# 06_LEDs.net
KiCad netlist of a schematic drawn in Altium Designer
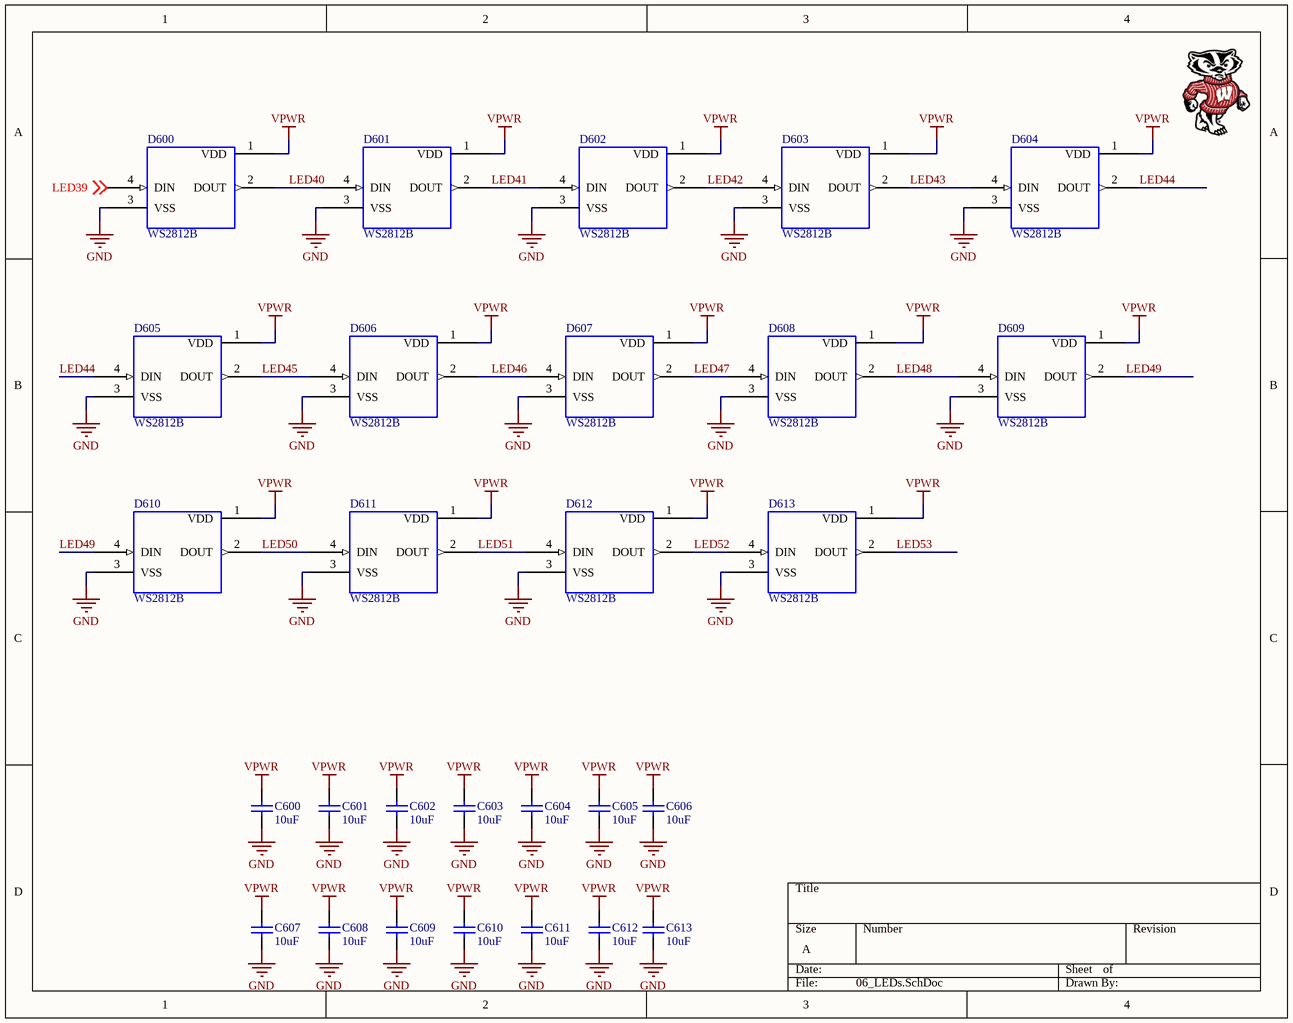
[diagram p0: 06_LEDs.SchDoc]

(export (version "E")
  (design (tool "Eeschema 10.0.6"))
  (components
    (comp (ref "C600")
      (value "10uF")
      (footprint "CAP_0805")
      (description "CAP CER 10UF 16V X7R 0805")
      (fields
        (field (name "MANUFACTURER") "Samsung")
        (field (name "MANUFACTURER PART NUMBER") "CL21A106KPCLQNC")
        (field (name "CAPACITANCE") "10uF")
      )
      (libsource (lib "ece315-2018-fall") (part "CAP_0805_U_010.00"))
    )
    (comp (ref "C601")
      (value "10uF")
      (footprint "CAP_0805")
      (description "CAP CER 10UF 16V X7R 0805")
      (fields
        (field (name "MANUFACTURER") "Samsung")
        (field (name "MANUFACTURER PART NUMBER") "CL21A106KPCLQNC")
        (field (name "CAPACITANCE") "10uF")
      )
      (libsource (lib "ece315-2018-fall") (part "CAP_0805_U_010.00"))
    )
    (comp (ref "C602")
      (value "10uF")
      (footprint "CAP_0805")
      (description "CAP CER 10UF 16V X7R 0805")
      (fields
        (field (name "MANUFACTURER") "Samsung")
        (field (name "MANUFACTURER PART NUMBER") "CL21A106KPCLQNC")
        (field (name "CAPACITANCE") "10uF")
      )
      (libsource (lib "ece315-2018-fall") (part "CAP_0805_U_010.00"))
    )
    (comp (ref "C603")
      (value "10uF")
      (footprint "CAP_0805")
      (description "CAP CER 10UF 16V X7R 0805")
      (fields
        (field (name "MANUFACTURER") "Samsung")
        (field (name "MANUFACTURER PART NUMBER") "CL21A106KPCLQNC")
        (field (name "CAPACITANCE") "10uF")
      )
      (libsource (lib "ece315-2018-fall") (part "CAP_0805_U_010.00"))
    )
    (comp (ref "C604")
      (value "10uF")
      (footprint "CAP_0805")
      (description "CAP CER 10UF 16V X7R 0805")
      (fields
        (field (name "MANUFACTURER") "Samsung")
        (field (name "MANUFACTURER PART NUMBER") "CL21A106KPCLQNC")
        (field (name "CAPACITANCE") "10uF")
      )
      (libsource (lib "ece315-2018-fall") (part "CAP_0805_U_010.00"))
    )
    (comp (ref "C605")
      (value "10uF")
      (footprint "CAP_0805")
      (description "CAP CER 10UF 16V X7R 0805")
      (fields
        (field (name "MANUFACTURER") "Samsung")
        (field (name "MANUFACTURER PART NUMBER") "CL21A106KPCLQNC")
        (field (name "CAPACITANCE") "10uF")
      )
      (libsource (lib "ece315-2018-fall") (part "CAP_0805_U_010.00"))
    )
    (comp (ref "C606")
      (value "10uF")
      (footprint "CAP_0805")
      (description "CAP CER 10UF 16V X7R 0805")
      (fields
        (field (name "MANUFACTURER") "Samsung")
        (field (name "MANUFACTURER PART NUMBER") "CL21A106KPCLQNC")
        (field (name "CAPACITANCE") "10uF")
      )
      (libsource (lib "ece315-2018-fall") (part "CAP_0805_U_010.00"))
    )
    (comp (ref "C607")
      (value "10uF")
      (footprint "CAP_0805")
      (description "CAP CER 10UF 16V X7R 0805")
      (fields
        (field (name "MANUFACTURER") "Samsung")
        (field (name "MANUFACTURER PART NUMBER") "CL21A106KPCLQNC")
        (field (name "CAPACITANCE") "10uF")
      )
      (libsource (lib "ece315-2018-fall") (part "CAP_0805_U_010.00"))
    )
    (comp (ref "C608")
      (value "10uF")
      (footprint "CAP_0805")
      (description "CAP CER 10UF 16V X7R 0805")
      (fields
        (field (name "MANUFACTURER") "Samsung")
        (field (name "MANUFACTURER PART NUMBER") "CL21A106KPCLQNC")
        (field (name "CAPACITANCE") "10uF")
      )
      (libsource (lib "ece315-2018-fall") (part "CAP_0805_U_010.00"))
    )
    (comp (ref "C609")
      (value "10uF")
      (footprint "CAP_0805")
      (description "CAP CER 10UF 16V X7R 0805")
      (fields
        (field (name "MANUFACTURER") "Samsung")
        (field (name "MANUFACTURER PART NUMBER") "CL21A106KPCLQNC")
        (field (name "CAPACITANCE") "10uF")
      )
      (libsource (lib "ece315-2018-fall") (part "CAP_0805_U_010.00"))
    )
    (comp (ref "C610")
      (value "10uF")
      (footprint "CAP_0805")
      (description "CAP CER 10UF 16V X7R 0805")
      (fields
        (field (name "MANUFACTURER") "Samsung")
        (field (name "MANUFACTURER PART NUMBER") "CL21A106KPCLQNC")
        (field (name "CAPACITANCE") "10uF")
      )
      (libsource (lib "ece315-2018-fall") (part "CAP_0805_U_010.00"))
    )
    (comp (ref "C611")
      (value "10uF")
      (footprint "CAP_0805")
      (description "CAP CER 10UF 16V X7R 0805")
      (fields
        (field (name "MANUFACTURER") "Samsung")
        (field (name "MANUFACTURER PART NUMBER") "CL21A106KPCLQNC")
        (field (name "CAPACITANCE") "10uF")
      )
      (libsource (lib "ece315-2018-fall") (part "CAP_0805_U_010.00"))
    )
    (comp (ref "C612")
      (value "10uF")
      (footprint "CAP_0805")
      (description "CAP CER 10UF 16V X7R 0805")
      (fields
        (field (name "MANUFACTURER") "Samsung")
        (field (name "MANUFACTURER PART NUMBER") "CL21A106KPCLQNC")
        (field (name "CAPACITANCE") "10uF")
      )
      (libsource (lib "ece315-2018-fall") (part "CAP_0805_U_010.00"))
    )
    (comp (ref "C613")
      (value "10uF")
      (footprint "CAP_0805")
      (description "CAP CER 10UF 16V X7R 0805")
      (fields
        (field (name "MANUFACTURER") "Samsung")
        (field (name "MANUFACTURER PART NUMBER") "CL21A106KPCLQNC")
        (field (name "CAPACITANCE") "10uF")
      )
      (libsource (lib "ece315-2018-fall") (part "CAP_0805_U_010.00"))
    )
    (comp (ref "D600")
      (value "WS2812B")
      (footprint "WS2812B")
      (description "LED RGB WS2812B")
      (fields (field (name "MANUFACTURER PART NUMBER") "EBAY"))
      (libsource (lib "LEDs") (part "WS2812B"))
    )
    (comp (ref "D601")
      (value "WS2812B")
      (footprint "WS2812B")
      (description "LED RGB WS2812B")
      (fields (field (name "MANUFACTURER PART NUMBER") "EBAY"))
      (libsource (lib "LEDs") (part "WS2812B"))
    )
    (comp (ref "D602")
      (value "WS2812B")
      (footprint "WS2812B")
      (description "LED RGB WS2812B")
      (fields (field (name "MANUFACTURER PART NUMBER") "EBAY"))
      (libsource (lib "LEDs") (part "WS2812B"))
    )
    (comp (ref "D603")
      (value "WS2812B")
      (footprint "WS2812B")
      (description "LED RGB WS2812B")
      (fields (field (name "MANUFACTURER PART NUMBER") "EBAY"))
      (libsource (lib "LEDs") (part "WS2812B"))
    )
    (comp (ref "D604")
      (value "WS2812B")
      (footprint "WS2812B")
      (description "LED RGB WS2812B")
      (fields (field (name "MANUFACTURER PART NUMBER") "EBAY"))
      (libsource (lib "LEDs") (part "WS2812B"))
    )
    (comp (ref "D605")
      (value "WS2812B")
      (footprint "WS2812B")
      (description "LED RGB WS2812B")
      (fields (field (name "MANUFACTURER PART NUMBER") "EBAY"))
      (libsource (lib "LEDs") (part "WS2812B"))
    )
    (comp (ref "D606")
      (value "WS2812B")
      (footprint "WS2812B")
      (description "LED RGB WS2812B")
      (fields (field (name "MANUFACTURER PART NUMBER") "EBAY"))
      (libsource (lib "LEDs") (part "WS2812B"))
    )
    (comp (ref "D607")
      (value "WS2812B")
      (footprint "WS2812B")
      (description "LED RGB WS2812B")
      (fields (field (name "MANUFACTURER PART NUMBER") "EBAY"))
      (libsource (lib "LEDs") (part "WS2812B"))
    )
    (comp (ref "D608")
      (value "WS2812B")
      (footprint "WS2812B")
      (description "LED RGB WS2812B")
      (fields (field (name "MANUFACTURER PART NUMBER") "EBAY"))
      (libsource (lib "LEDs") (part "WS2812B"))
    )
    (comp (ref "D609")
      (value "WS2812B")
      (footprint "WS2812B")
      (description "LED RGB WS2812B")
      (fields (field (name "MANUFACTURER PART NUMBER") "EBAY"))
      (libsource (lib "LEDs") (part "WS2812B"))
    )
    (comp (ref "D610")
      (value "WS2812B")
      (footprint "WS2812B")
      (description "LED RGB WS2812B")
      (fields (field (name "MANUFACTURER PART NUMBER") "EBAY"))
      (libsource (lib "LEDs") (part "WS2812B"))
    )
    (comp (ref "D611")
      (value "WS2812B")
      (footprint "WS2812B")
      (description "LED RGB WS2812B")
      (fields (field (name "MANUFACTURER PART NUMBER") "EBAY"))
      (libsource (lib "LEDs") (part "WS2812B"))
    )
    (comp (ref "D612")
      (value "WS2812B")
      (footprint "WS2812B")
      (description "LED RGB WS2812B")
      (fields (field (name "MANUFACTURER PART NUMBER") "EBAY"))
      (libsource (lib "LEDs") (part "WS2812B"))
    )
    (comp (ref "D613")
      (value "WS2812B")
      (footprint "WS2812B")
      (description "LED RGB WS2812B")
      (fields (field (name "MANUFACTURER PART NUMBER") "EBAY"))
      (libsource (lib "LEDs") (part "WS2812B"))
    )
  )
  (nets
    (net (code "1") (name "/LED40") (class "Default")
      (node (ref "D600") (pin "2") (pinfunction "DOUT_2") (pintype "output"))
      (node (ref "D601") (pin "4") (pinfunction "DIN_4") (pintype "input"))
    )
    (net (code "2") (name "/LED41") (class "Default")
      (node (ref "D601") (pin "2") (pinfunction "DOUT_2") (pintype "output"))
      (node (ref "D602") (pin "4") (pinfunction "DIN_4") (pintype "input"))
    )
    (net (code "3") (name "/LED42") (class "Default")
      (node (ref "D602") (pin "2") (pinfunction "DOUT_2") (pintype "output"))
      (node (ref "D603") (pin "4") (pinfunction "DIN_4") (pintype "input"))
    )
    (net (code "4") (name "/LED43") (class "Default")
      (node (ref "D603") (pin "2") (pinfunction "DOUT_2") (pintype "output"))
      (node (ref "D604") (pin "4") (pinfunction "DIN_4") (pintype "input"))
    )
    (net (code "5") (name "/LED44") (class "Default")
      (node (ref "D604") (pin "2") (pinfunction "DOUT_2") (pintype "output"))
      (node (ref "D605") (pin "4") (pinfunction "DIN_4") (pintype "input"))
    )
    (net (code "6") (name "/LED45") (class "Default")
      (node (ref "D605") (pin "2") (pinfunction "DOUT_2") (pintype "output"))
      (node (ref "D606") (pin "4") (pinfunction "DIN_4") (pintype "input"))
    )
    (net (code "7") (name "/LED46") (class "Default")
      (node (ref "D606") (pin "2") (pinfunction "DOUT_2") (pintype "output"))
      (node (ref "D607") (pin "4") (pinfunction "DIN_4") (pintype "input"))
    )
    (net (code "8") (name "/LED47") (class "Default")
      (node (ref "D607") (pin "2") (pinfunction "DOUT_2") (pintype "output"))
      (node (ref "D608") (pin "4") (pinfunction "DIN_4") (pintype "input"))
    )
    (net (code "9") (name "/LED48") (class "Default")
      (node (ref "D608") (pin "2") (pinfunction "DOUT_2") (pintype "output"))
      (node (ref "D609") (pin "4") (pinfunction "DIN_4") (pintype "input"))
    )
    (net (code "10") (name "/LED49") (class "Default")
      (node (ref "D609") (pin "2") (pinfunction "DOUT_2") (pintype "output"))
      (node (ref "D610") (pin "4") (pinfunction "DIN_4") (pintype "input"))
    )
    (net (code "11") (name "/LED50") (class "Default")
      (node (ref "D610") (pin "2") (pinfunction "DOUT_2") (pintype "output"))
      (node (ref "D611") (pin "4") (pinfunction "DIN_4") (pintype "input"))
    )
    (net (code "12") (name "/LED51") (class "Default")
      (node (ref "D611") (pin "2") (pinfunction "DOUT_2") (pintype "output"))
      (node (ref "D612") (pin "4") (pinfunction "DIN_4") (pintype "input"))
    )
    (net (code "13") (name "/LED52") (class "Default")
      (node (ref "D612") (pin "2") (pinfunction "DOUT_2") (pintype "output"))
      (node (ref "D613") (pin "4") (pinfunction "DIN_4") (pintype "input"))
    )
    (net (code "14") (name "/LED53") (class "Default")
      (node (ref "D613") (pin "2") (pinfunction "DOUT_2") (pintype "output"))
    )
    (net (code "15") (name "GND") (class "Default")
      (node (ref "C600") (pin "1") (pinfunction "1_1") (pintype "passive"))
      (node (ref "C601") (pin "1") (pinfunction "1_1") (pintype "passive"))
      (node (ref "C602") (pin "1") (pinfunction "1_1") (pintype "passive"))
      (node (ref "C603") (pin "1") (pinfunction "1_1") (pintype "passive"))
      (node (ref "C604") (pin "1") (pinfunction "1_1") (pintype "passive"))
      (node (ref "C605") (pin "1") (pinfunction "1_1") (pintype "passive"))
      (node (ref "C606") (pin "1") (pinfunction "1_1") (pintype "passive"))
      (node (ref "C607") (pin "1") (pinfunction "1_1") (pintype "passive"))
      (node (ref "C608") (pin "1") (pinfunction "1_1") (pintype "passive"))
      (node (ref "C609") (pin "1") (pinfunction "1_1") (pintype "passive"))
      (node (ref "C610") (pin "1") (pinfunction "1_1") (pintype "passive"))
      (node (ref "C611") (pin "1") (pinfunction "1_1") (pintype "passive"))
      (node (ref "C612") (pin "1") (pinfunction "1_1") (pintype "passive"))
      (node (ref "C613") (pin "1") (pinfunction "1_1") (pintype "passive"))
      (node (ref "D600") (pin "3") (pinfunction "VSS_3") (pintype "power_in"))
      (node (ref "D601") (pin "3") (pinfunction "VSS_3") (pintype "power_in"))
      (node (ref "D602") (pin "3") (pinfunction "VSS_3") (pintype "power_in"))
      (node (ref "D603") (pin "3") (pinfunction "VSS_3") (pintype "power_in"))
      (node (ref "D604") (pin "3") (pinfunction "VSS_3") (pintype "power_in"))
      (node (ref "D605") (pin "3") (pinfunction "VSS_3") (pintype "power_in"))
      (node (ref "D606") (pin "3") (pinfunction "VSS_3") (pintype "power_in"))
      (node (ref "D607") (pin "3") (pinfunction "VSS_3") (pintype "power_in"))
      (node (ref "D608") (pin "3") (pinfunction "VSS_3") (pintype "power_in"))
      (node (ref "D609") (pin "3") (pinfunction "VSS_3") (pintype "power_in"))
      (node (ref "D610") (pin "3") (pinfunction "VSS_3") (pintype "power_in"))
      (node (ref "D611") (pin "3") (pinfunction "VSS_3") (pintype "power_in"))
      (node (ref "D612") (pin "3") (pinfunction "VSS_3") (pintype "power_in"))
      (node (ref "D613") (pin "3") (pinfunction "VSS_3") (pintype "power_in"))
    )
    (net (code "16") (name "LED39") (class "Default")
      (node (ref "D600") (pin "4") (pinfunction "DIN_4") (pintype "input"))
    )
    (net (code "17") (name "VPWR") (class "Default")
      (node (ref "C600") (pin "2") (pinfunction "2_2") (pintype "passive"))
      (node (ref "C601") (pin "2") (pinfunction "2_2") (pintype "passive"))
      (node (ref "C602") (pin "2") (pinfunction "2_2") (pintype "passive"))
      (node (ref "C603") (pin "2") (pinfunction "2_2") (pintype "passive"))
      (node (ref "C604") (pin "2") (pinfunction "2_2") (pintype "passive"))
      (node (ref "C605") (pin "2") (pinfunction "2_2") (pintype "passive"))
      (node (ref "C606") (pin "2") (pinfunction "2_2") (pintype "passive"))
      (node (ref "C607") (pin "2") (pinfunction "2_2") (pintype "passive"))
      (node (ref "C608") (pin "2") (pinfunction "2_2") (pintype "passive"))
      (node (ref "C609") (pin "2") (pinfunction "2_2") (pintype "passive"))
      (node (ref "C610") (pin "2") (pinfunction "2_2") (pintype "passive"))
      (node (ref "C611") (pin "2") (pinfunction "2_2") (pintype "passive"))
      (node (ref "C612") (pin "2") (pinfunction "2_2") (pintype "passive"))
      (node (ref "C613") (pin "2") (pinfunction "2_2") (pintype "passive"))
      (node (ref "D600") (pin "1") (pinfunction "VDD_1") (pintype "power_in"))
      (node (ref "D601") (pin "1") (pinfunction "VDD_1") (pintype "power_in"))
      (node (ref "D602") (pin "1") (pinfunction "VDD_1") (pintype "power_in"))
      (node (ref "D603") (pin "1") (pinfunction "VDD_1") (pintype "power_in"))
      (node (ref "D604") (pin "1") (pinfunction "VDD_1") (pintype "power_in"))
      (node (ref "D605") (pin "1") (pinfunction "VDD_1") (pintype "power_in"))
      (node (ref "D606") (pin "1") (pinfunction "VDD_1") (pintype "power_in"))
      (node (ref "D607") (pin "1") (pinfunction "VDD_1") (pintype "power_in"))
      (node (ref "D608") (pin "1") (pinfunction "VDD_1") (pintype "power_in"))
      (node (ref "D609") (pin "1") (pinfunction "VDD_1") (pintype "power_in"))
      (node (ref "D610") (pin "1") (pinfunction "VDD_1") (pintype "power_in"))
      (node (ref "D611") (pin "1") (pinfunction "VDD_1") (pintype "power_in"))
      (node (ref "D612") (pin "1") (pinfunction "VDD_1") (pintype "power_in"))
      (node (ref "D613") (pin "1") (pinfunction "VDD_1") (pintype "power_in"))
    )
  )
)
